# PowerSupplies.net
KiCad netlist of a schematic drawn in Altium Designer
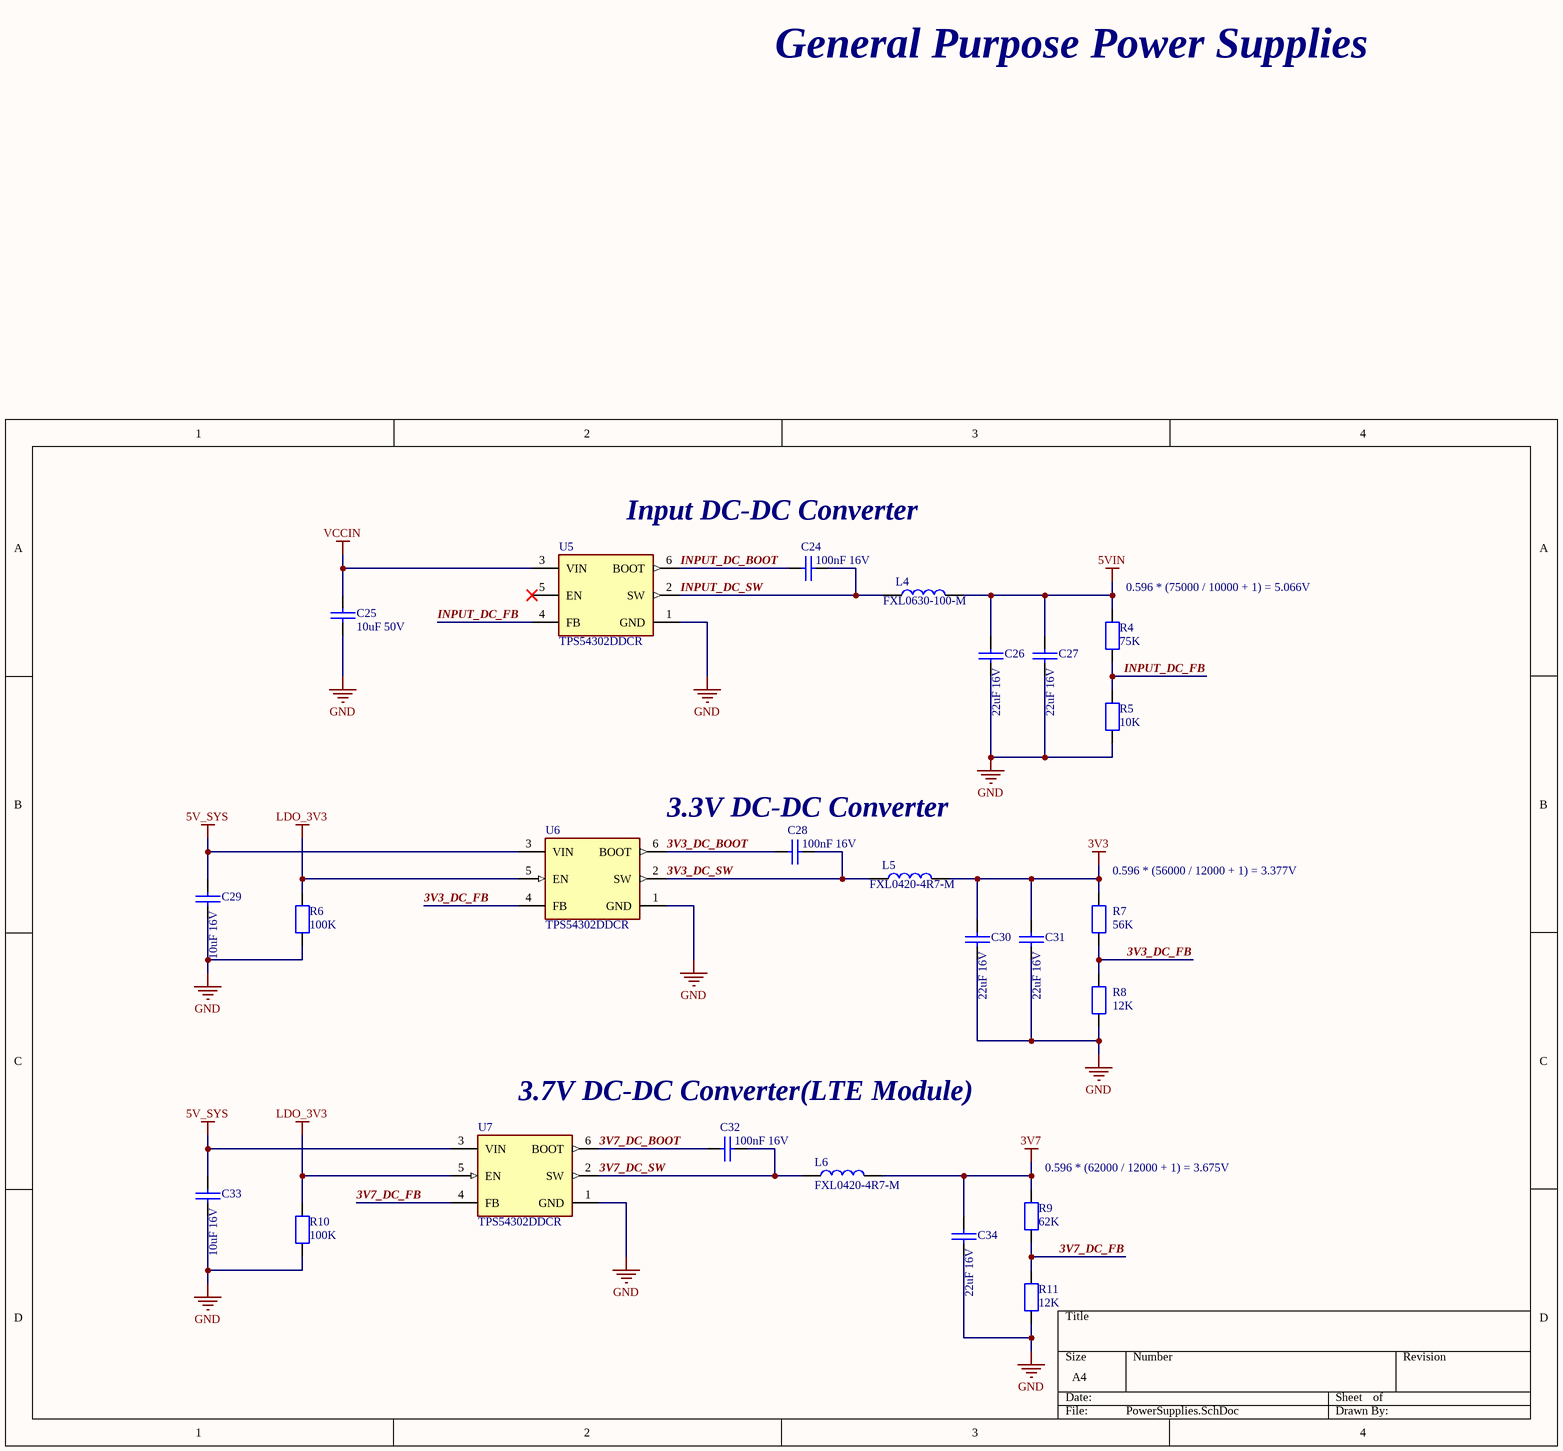
[diagram p0: PowerSupplies.SchDoc]

(export (version "E")
  (design (tool "Eeschema 10.0.6"))
  (components
    (comp (ref "C24")
      (value "100nF 16V")
      (footprint "C_0402")
      (description "Capacitor 0402 SMD")
      (libsource (lib "tor1kkLib") (part "C_0402"))
    )
    (comp (ref "C25")
      (value "10uF 50V")
      (footprint "C_1206")
      (description "Capacitor 1206 SMD")
      (libsource (lib "tor1kkLib") (part "C_1206"))
    )
    (comp (ref "C26")
      (value "22uF 16V")
      (footprint "C_0603")
      (description "Capacitor 0603 SMD")
      (libsource (lib "tor1kkLib") (part "C_0603"))
    )
    (comp (ref "C27")
      (value "22uF 16V")
      (footprint "C_0603")
      (description "Capacitor 0603 SMD")
      (libsource (lib "tor1kkLib") (part "C_0603"))
    )
    (comp (ref "C28")
      (value "100nF 16V")
      (footprint "C_0402")
      (description "Capacitor 0402 SMD")
      (libsource (lib "tor1kkLib") (part "C_0402"))
    )
    (comp (ref "C29")
      (value "10uF 16V")
      (footprint "C_0603")
      (description "Capacitor 0603 SMD")
      (libsource (lib "tor1kkLib") (part "C_0603"))
    )
    (comp (ref "C30")
      (value "22uF 16V")
      (footprint "C_0603")
      (description "Capacitor 0603 SMD")
      (libsource (lib "tor1kkLib") (part "C_0603"))
    )
    (comp (ref "C31")
      (value "22uF 16V")
      (footprint "C_0603")
      (description "Capacitor 0603 SMD")
      (libsource (lib "tor1kkLib") (part "C_0603"))
    )
    (comp (ref "C32")
      (value "100nF 16V")
      (footprint "C_0402")
      (description "Capacitor 0402 SMD")
      (libsource (lib "tor1kkLib") (part "C_0402"))
    )
    (comp (ref "C33")
      (value "10uF 16V")
      (footprint "C_0603")
      (description "Capacitor 0603 SMD")
      (libsource (lib "tor1kkLib") (part "C_0603"))
    )
    (comp (ref "C34")
      (value "22uF 16V")
      (footprint "C_0603")
      (description "Capacitor 0603 SMD")
      (libsource (lib "tor1kkLib") (part "C_0603"))
    )
    (comp (ref "L4")
      (value "FXL0630-100-M")
      (footprint "FXL0630")
      (description "4.5A 10uH Winding Inductor ±20% 5.5A SMD,6.6x7mm Power Inductors ROHS")
      (fields
        (field (name "MANUFACTURER") "cjiang")
        (field (name "MANUFACTURER PART NUMBER") "FXL0630-150-M")
      )
      (libsource (lib "tor1kkLib") (part "FXL0630-100-M"))
    )
    (comp (ref "L5")
      (value "FXL0420-4R7-M")
      (footprint "FXL0420")
      (description "2.8A 4.7uH Winding Inductor ±20% 3A SMD,4.2x4.4mm Power Inductors ROHS")
      (fields
        (field (name "MANUFACTURER") "cjiang (Changjiang Microelectronics Tech)")
        (field (name "MFR. PART") "FXL0420-100-M")
      )
      (libsource (lib "tor1kkLib") (part "FXL0420-4R7-M"))
    )
    (comp (ref "L6")
      (value "FXL0420-4R7-M")
      (footprint "FXL0420")
      (description "2.8A 4.7uH Winding Inductor ±20% 3A SMD,4.2x4.4mm Power Inductors ROHS")
      (fields
        (field (name "MANUFACTURER") "cjiang (Changjiang Microelectronics Tech)")
        (field (name "MFR. PART") "FXL0420-100-M")
      )
      (libsource (lib "tor1kkLib") (part "FXL0420-4R7-M"))
    )
    (comp (ref "R4")
      (value "75K")
      (footprint "R_0603")
      (description "Resistor 0603 SMD")
      (libsource (lib "tor1kkLib") (part "R_0603"))
    )
    (comp (ref "R5")
      (value "10K")
      (footprint "R_0603")
      (description "Resistor 0603 SMD")
      (libsource (lib "tor1kkLib") (part "R_0603"))
    )
    (comp (ref "R6")
      (value "100K")
      (footprint "R_0603")
      (description "Resistor 0603 SMD")
      (libsource (lib "tor1kkLib") (part "R_0603"))
    )
    (comp (ref "R7")
      (value "56K")
      (footprint "R_0603")
      (description "Resistor 0603 SMD")
      (libsource (lib "tor1kkLib") (part "R_0603"))
    )
    (comp (ref "R8")
      (value "12K")
      (footprint "R_0603")
      (description "Resistor 0603 SMD")
      (libsource (lib "tor1kkLib") (part "R_0603"))
    )
    (comp (ref "R9")
      (value "62K")
      (footprint "R_0603")
      (description "Resistor 0603 SMD")
      (libsource (lib "tor1kkLib") (part "R_0603"))
    )
    (comp (ref "R10")
      (value "100K")
      (footprint "R_0603")
      (description "Resistor 0603 SMD")
      (libsource (lib "tor1kkLib") (part "R_0603"))
    )
    (comp (ref "R11")
      (value "12K")
      (footprint "R_0603")
      (description "Resistor 0603 SMD")
      (libsource (lib "tor1kkLib") (part "R_0603"))
    )
    (comp (ref "U5")
      (value "TPS54302DDCR")
      (footprint "FP-DDC0006A-MFG")
      (description "IC REG BUCK ADJ 3A TSOT23-6")
      (fields
        (field (name "MANUFACTURER") "Texas Instruments")
        (field (name "OCTOPART") "https://octopart.com/tps54302ddcr-texas+instruments-74209025")
      )
      (libsource (lib "Altium Content Vault") (part "e6e62595b56d4ede9a2c24ebe42f01f"))
    )
    (comp (ref "U6")
      (value "TPS54302DDCR")
      (footprint "FP-DDC0006A-MFG")
      (description "IC REG BUCK ADJ 3A TSOT23-6")
      (fields
        (field (name "MANUFACTURER") "Texas Instruments")
        (field (name "OCTOPART") "https://octopart.com/tps54302ddcr-texas+instruments-74209025")
      )
      (libsource (lib "Altium Content Vault") (part "e6e62595b56d4ede9a2c24ebe42f01f"))
    )
    (comp (ref "U7")
      (value "TPS54302DDCR")
      (footprint "FP-DDC0006A-MFG")
      (description "IC REG BUCK ADJ 3A TSOT23-6")
      (fields
        (field (name "MANUFACTURER") "Texas Instruments")
        (field (name "OCTOPART") "https://octopart.com/tps54302ddcr-texas+instruments-74209025")
      )
      (libsource (lib "Altium Content Vault") (part "e6e62595b56d4ede9a2c24ebe42f01f"))
    )
  )
  (nets
    (net (code "1") (name "/3V3_DC_BOOT") (class "Default")
      (node (ref "C28") (pin "1") (pintype "passive"))
      (node (ref "U6") (pin "6") (pinfunction "BOOT_6") (pintype "output"))
    )
    (net (code "2") (name "/3V3_DC_FB") (class "Default")
      (node (ref "R7") (pin "1") (pintype "passive"))
      (node (ref "R8") (pin "2") (pintype "passive"))
      (node (ref "U6") (pin "4") (pinfunction "FB_4") (pintype "passive"))
    )
    (net (code "3") (name "/3V3_DC_SW") (class "Default")
      (node (ref "C28") (pin "2") (pintype "passive"))
      (node (ref "L5") (pin "1") (pintype "passive"))
      (node (ref "U6") (pin "2") (pinfunction "SW_2") (pintype "output"))
    )
    (net (code "4") (name "/3V7_DC_BOOT") (class "Default")
      (node (ref "C32") (pin "1") (pintype "passive"))
      (node (ref "U7") (pin "6") (pinfunction "BOOT_6") (pintype "output"))
    )
    (net (code "5") (name "/3V7_DC_FB") (class "Default")
      (node (ref "R11") (pin "2") (pintype "passive"))
      (node (ref "R9") (pin "1") (pintype "passive"))
      (node (ref "U7") (pin "4") (pinfunction "FB_4") (pintype "passive"))
    )
    (net (code "6") (name "/3V7_DC_SW") (class "Default")
      (node (ref "C32") (pin "2") (pintype "passive"))
      (node (ref "L6") (pin "1") (pintype "passive"))
      (node (ref "U7") (pin "2") (pinfunction "SW_2") (pintype "output"))
    )
    (net (code "7") (name "/INPUT_DC_BOOT") (class "Default")
      (node (ref "C24") (pin "1") (pintype "passive"))
      (node (ref "U5") (pin "6") (pinfunction "BOOT_6") (pintype "output"))
    )
    (net (code "8") (name "/INPUT_DC_FB") (class "Default")
      (node (ref "R4") (pin "1") (pintype "passive"))
      (node (ref "R5") (pin "2") (pintype "passive"))
      (node (ref "U5") (pin "4") (pinfunction "FB_4") (pintype "passive"))
    )
    (net (code "9") (name "/INPUT_DC_SW") (class "Default")
      (node (ref "C24") (pin "2") (pintype "passive"))
      (node (ref "L4") (pin "1") (pintype "passive"))
      (node (ref "U5") (pin "2") (pinfunction "SW_2") (pintype "output"))
    )
    (net (code "10") (name "3V3") (class "Default")
      (node (ref "C30") (pin "1") (pintype "passive"))
      (node (ref "C31") (pin "1") (pintype "passive"))
      (node (ref "L5") (pin "2") (pintype "passive"))
      (node (ref "R7") (pin "2") (pintype "passive"))
    )
    (net (code "11") (name "3V7") (class "Default")
      (node (ref "C34") (pin "1") (pintype "passive"))
      (node (ref "L6") (pin "2") (pintype "passive"))
      (node (ref "R9") (pin "2") (pintype "passive"))
    )
    (net (code "12") (name "5VIN") (class "Default")
      (node (ref "C26") (pin "1") (pintype "passive"))
      (node (ref "C27") (pin "1") (pintype "passive"))
      (node (ref "L4") (pin "2") (pintype "passive"))
      (node (ref "R4") (pin "2") (pintype "passive"))
    )
    (net (code "13") (name "5V_SYS") (class "Default")
      (node (ref "C29") (pin "1") (pintype "passive"))
      (node (ref "C33") (pin "1") (pintype "passive"))
      (node (ref "U6") (pin "3") (pinfunction "VIN_3") (pintype "power_in"))
      (node (ref "U7") (pin "3") (pinfunction "VIN_3") (pintype "power_in"))
    )
    (net (code "14") (name "GND") (class "Default")
      (node (ref "C25") (pin "2") (pintype "passive"))
      (node (ref "C26") (pin "2") (pintype "passive"))
      (node (ref "C27") (pin "2") (pintype "passive"))
      (node (ref "C29") (pin "2") (pintype "passive"))
      (node (ref "C30") (pin "2") (pintype "passive"))
      (node (ref "C31") (pin "2") (pintype "passive"))
      (node (ref "C33") (pin "2") (pintype "passive"))
      (node (ref "C34") (pin "2") (pintype "passive"))
      (node (ref "R10") (pin "1") (pintype "passive"))
      (node (ref "R11") (pin "1") (pintype "passive"))
      (node (ref "R5") (pin "1") (pintype "passive"))
      (node (ref "R6") (pin "1") (pintype "passive"))
      (node (ref "R8") (pin "1") (pintype "passive"))
      (node (ref "U5") (pin "1") (pinfunction "GND_1") (pintype "power_in"))
      (node (ref "U6") (pin "1") (pinfunction "GND_1") (pintype "power_in"))
      (node (ref "U7") (pin "1") (pinfunction "GND_1") (pintype "power_in"))
    )
    (net (code "15") (name "LDO_3V3") (class "Default")
      (node (ref "R10") (pin "2") (pintype "passive"))
      (node (ref "R6") (pin "2") (pintype "passive"))
      (node (ref "U6") (pin "5") (pinfunction "EN_5") (pintype "passive"))
      (node (ref "U7") (pin "5") (pinfunction "EN_5") (pintype "passive"))
    )
    (net (code "16") (name "VCCIN") (class "Default")
      (node (ref "C25") (pin "1") (pintype "passive"))
      (node (ref "U5") (pin "3") (pinfunction "VIN_3") (pintype "power_in"))
    )
    (net (code "17") (name "unconnected-(U5-EN-Pad5)") (class "Default")
      (node (ref "U5") (pin "5") (pinfunction "EN_5") (pintype "passive+no_connect"))
    )
  )
)
